# 3_3.net
KiCad netlist of a schematic drawn in EAGLE
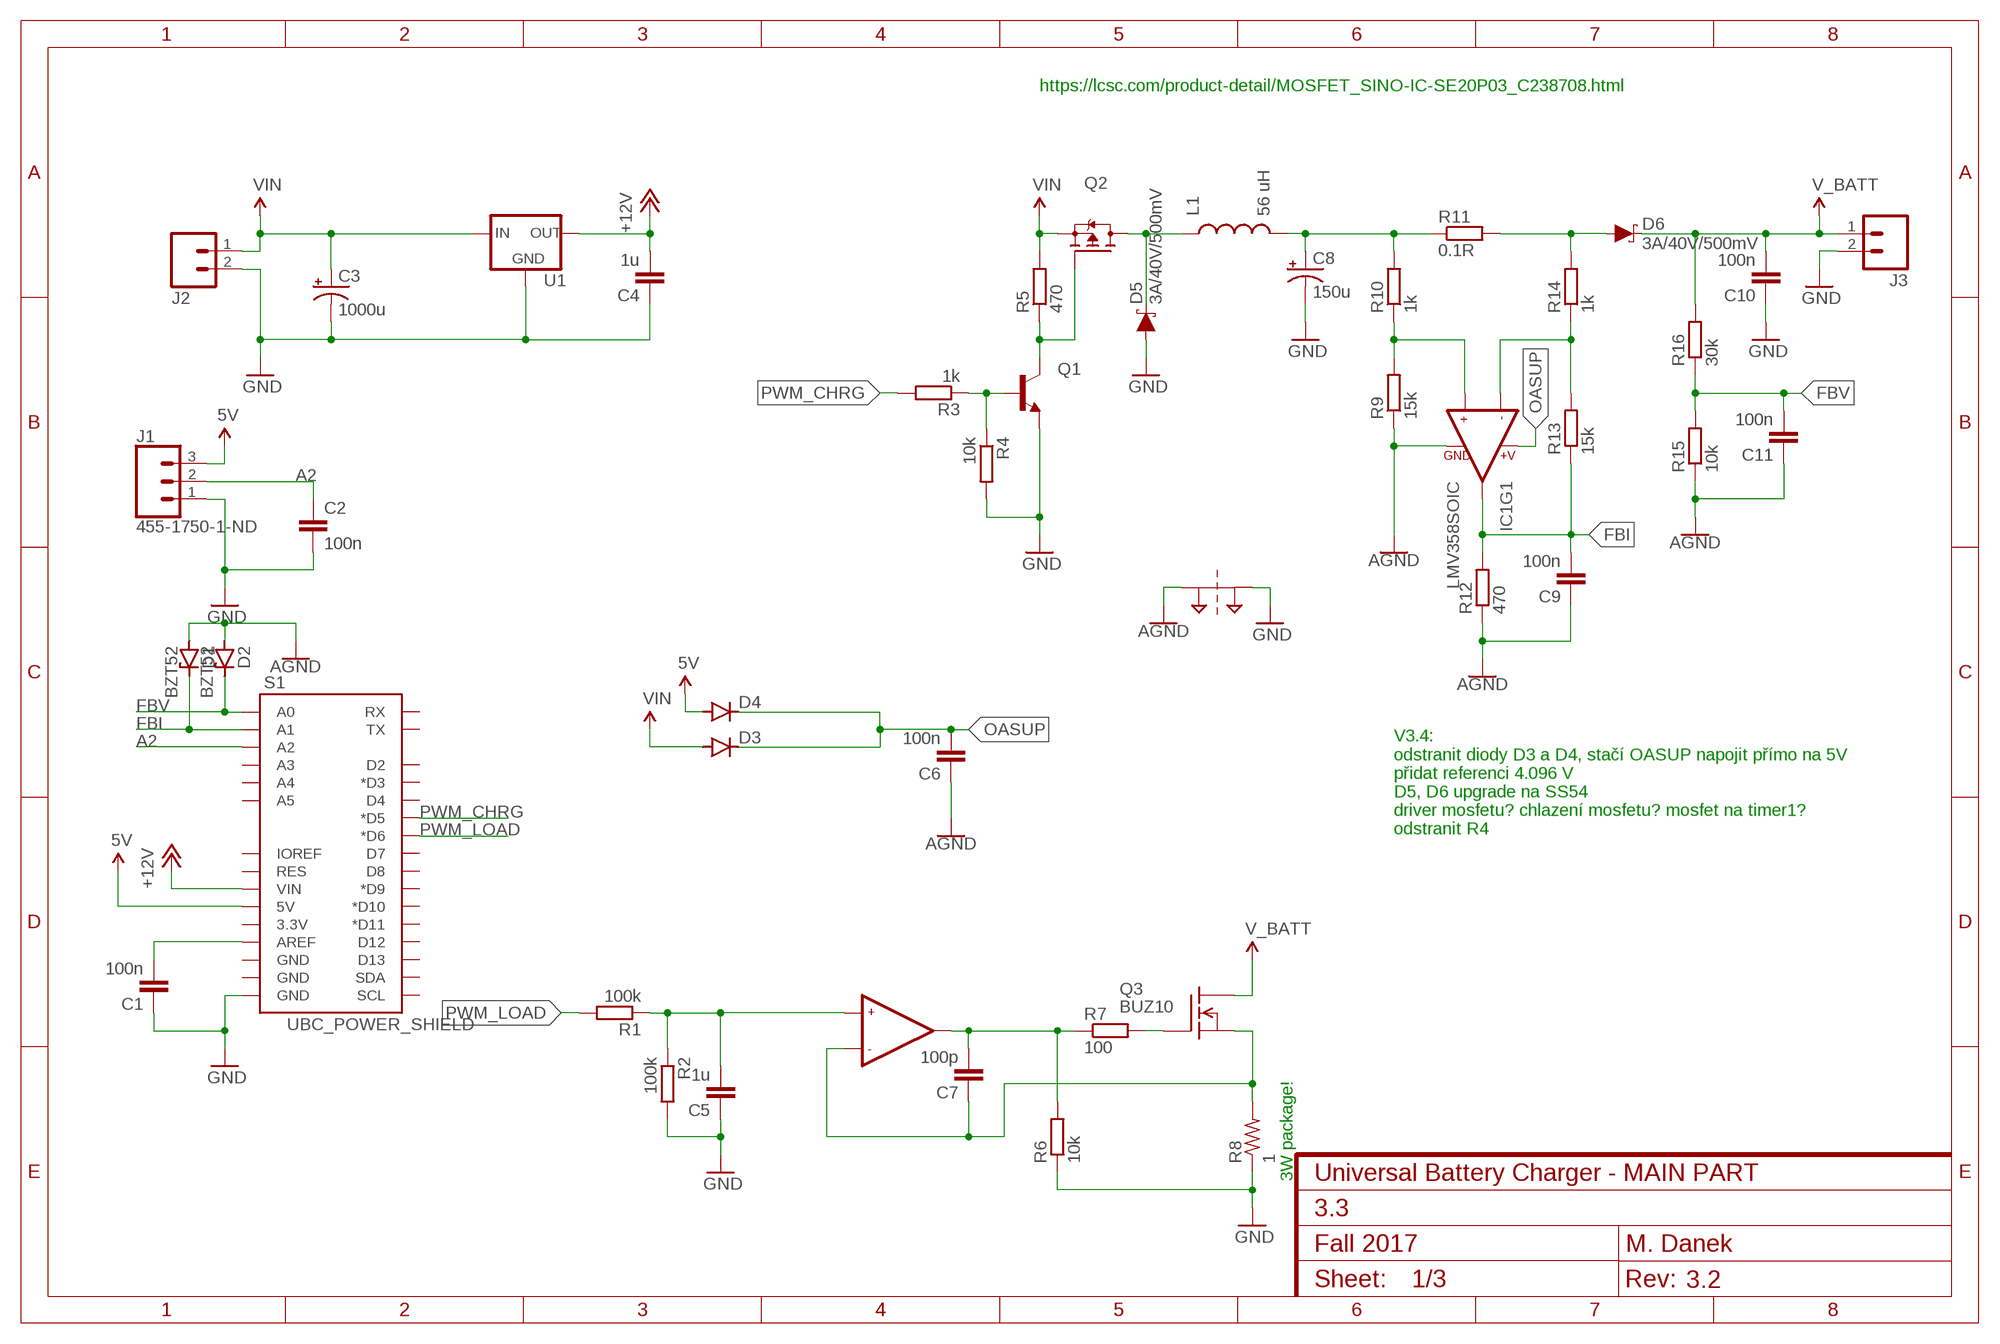
[diagram p0: schematic, sheet 1]
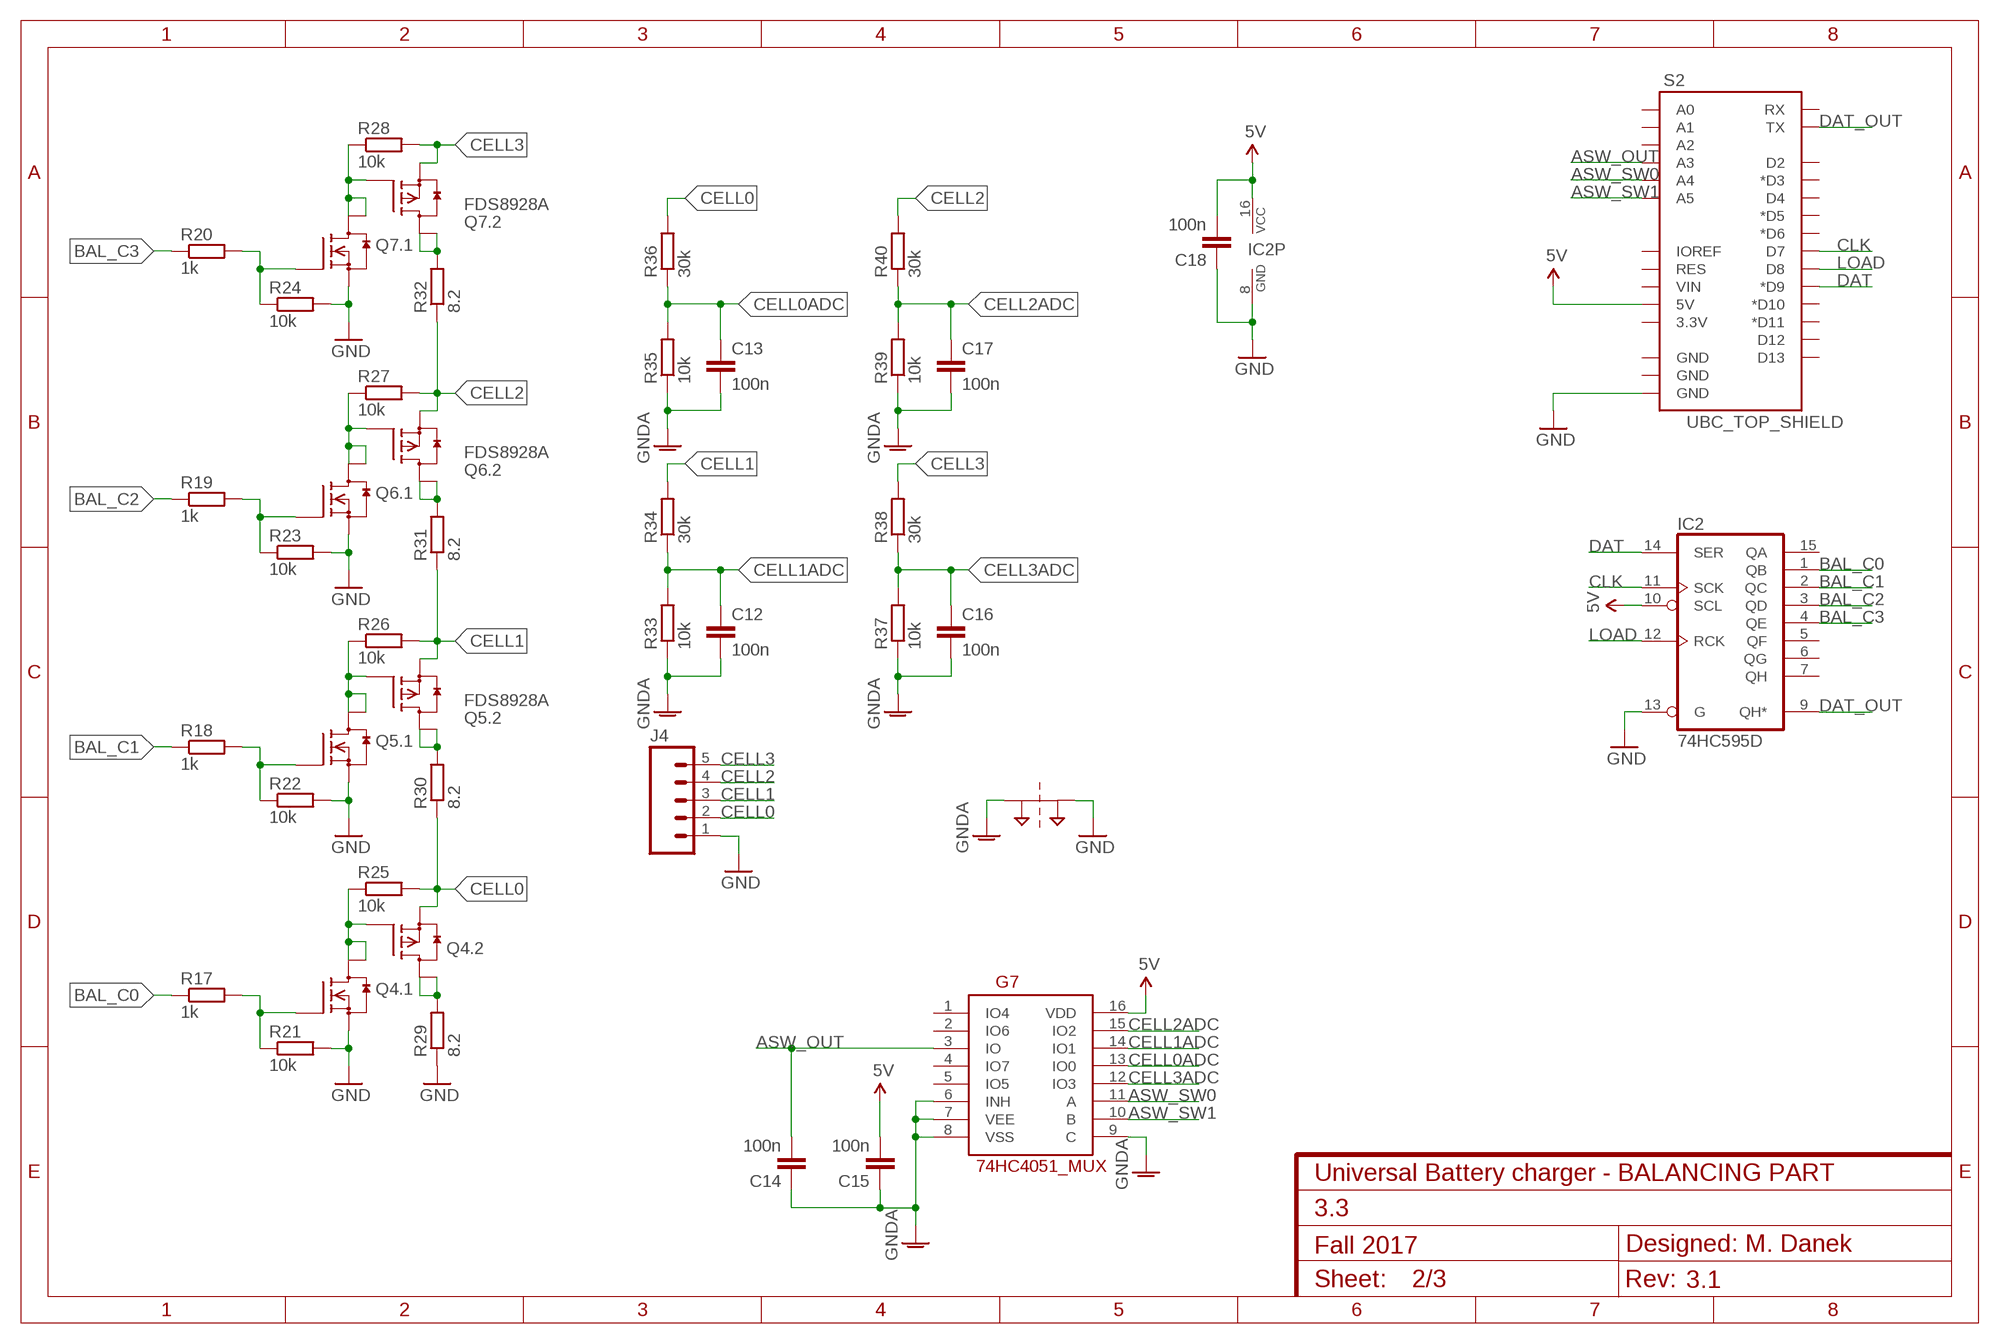
[diagram p1: schematic, sheet 2]
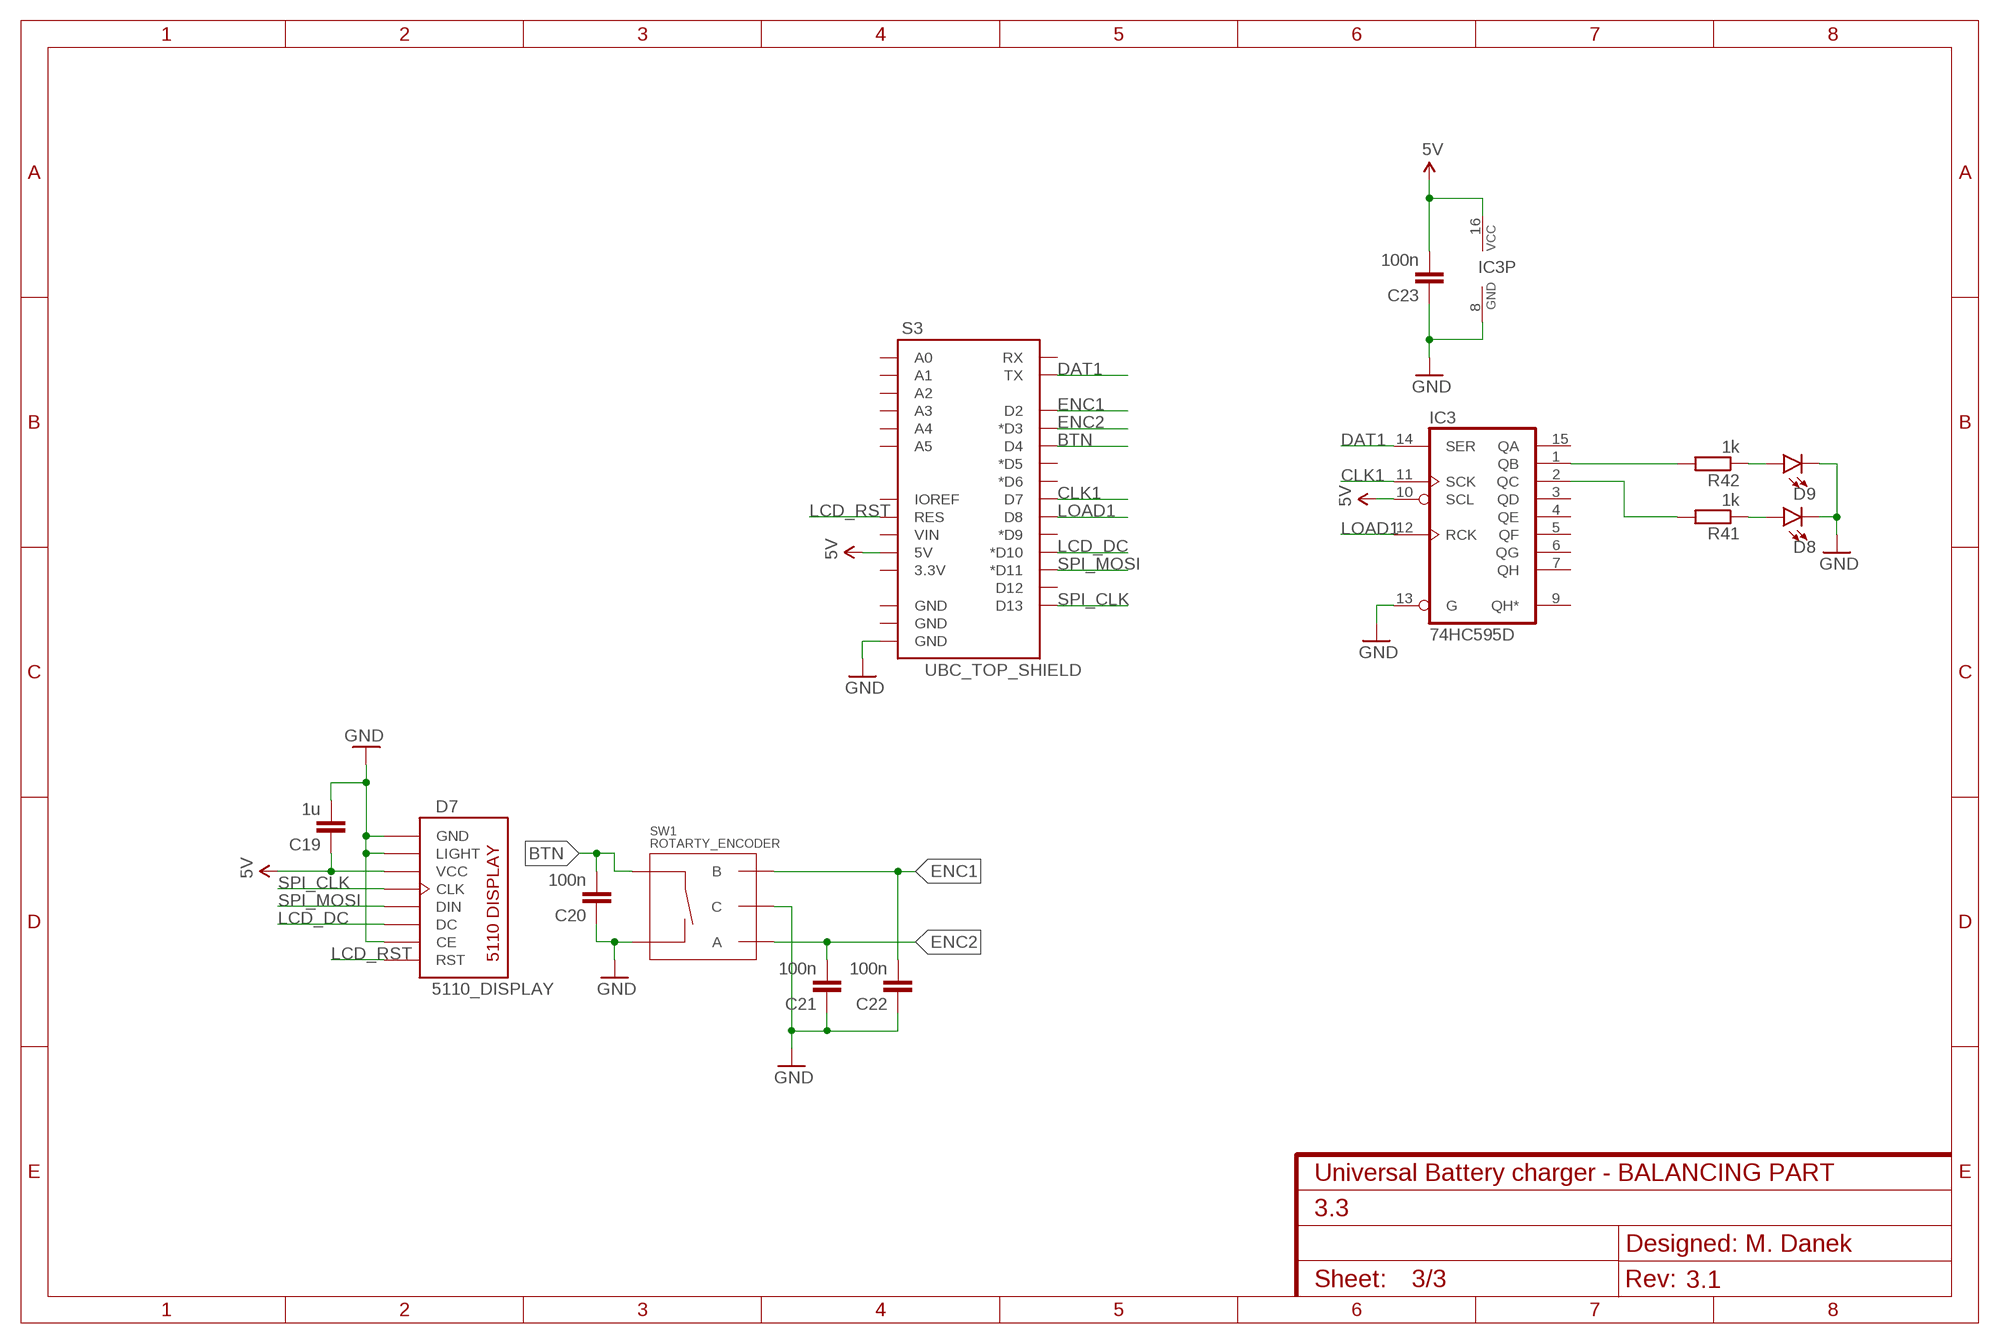
[diagram p2: schematic, sheet 3]

(export (version "E")
  (design (tool "Eeschema 10.0.6"))
  (components
    (comp (ref "C12")
      (value "100n")
      (footprint "eagle-import:C1206")
      (libsource (lib "eagle-import") (part "C-EUC1206"))
    )
    (comp (ref "C13")
      (value "100n")
      (footprint "eagle-import:C1206")
      (libsource (lib "eagle-import") (part "C-EUC1206"))
    )
    (comp (ref "C14")
      (value "100n")
      (footprint "eagle-import:C1206")
      (libsource (lib "eagle-import") (part "C-EUC1206"))
    )
    (comp (ref "C15")
      (value "100n")
      (footprint "eagle-import:C1206")
      (libsource (lib "eagle-import") (part "C-EUC1206"))
    )
    (comp (ref "C16")
      (value "100n")
      (footprint "eagle-import:C1206")
      (libsource (lib "eagle-import") (part "C-EUC1206"))
    )
    (comp (ref "C17")
      (value "100n")
      (footprint "eagle-import:C1206")
      (libsource (lib "eagle-import") (part "C-EUC1206"))
    )
    (comp (ref "C18")
      (value "100n")
      (footprint "eagle-import:1206")
      (libsource (lib "eagle-import") (part "CAP1206"))
    )
    (comp (ref "G7")
      (value "74HC4051_MUX")
      (footprint "eagle-import:SO16")
      (libsource (lib "eagle-import") (part "74HC4051_MUX"))
    )
    (comp (ref "IC2")
      (value "74HC595D")
      (footprint "eagle-import:SO16")
      (libsource (lib "eagle-import") (part "74595DHC"))
    )
    (comp (ref "J4")
      (value "M05PTH")
      (footprint "eagle-import:1X05")
      (libsource (lib "eagle-import") (part "M05PTH"))
    )
    (comp (ref "PT2")
      (value "2PT_GND_TIE")
      (footprint "eagle-import:2PT_GND_TIE")
      (libsource (lib "eagle-import") (part "2PT_GND_TIE"))
    )
    (comp (ref "Q4")
      (value "FDS8928A")
      (footprint "eagle-import:SO-8")
      (libsource (lib "eagle-import") (part "FDS8928A"))
    )
    (comp (ref "Q5")
      (value "FDS8928A")
      (footprint "eagle-import:SO-8")
      (libsource (lib "eagle-import") (part "FDS8928A"))
    )
    (comp (ref "Q6")
      (value "FDS8928A")
      (footprint "eagle-import:SO-8")
      (libsource (lib "eagle-import") (part "FDS8928A"))
    )
    (comp (ref "Q7")
      (value "FDS8928A")
      (footprint "eagle-import:SO-8")
      (libsource (lib "eagle-import") (part "FDS8928A"))
    )
    (comp (ref "R17")
      (value "1k")
      (footprint "eagle-import:R1206")
      (libsource (lib "eagle-import") (part "R-EU_R1206"))
    )
    (comp (ref "R18")
      (value "1k")
      (footprint "eagle-import:R1206")
      (libsource (lib "eagle-import") (part "R-EU_R1206"))
    )
    (comp (ref "R19")
      (value "1k")
      (footprint "eagle-import:R1206")
      (libsource (lib "eagle-import") (part "R-EU_R1206"))
    )
    (comp (ref "R20")
      (value "1k")
      (footprint "eagle-import:R1206")
      (libsource (lib "eagle-import") (part "R-EU_R1206"))
    )
    (comp (ref "R21")
      (value "10k")
      (footprint "eagle-import:R1206")
      (libsource (lib "eagle-import") (part "R-EU_R1206"))
    )
    (comp (ref "R22")
      (value "10k")
      (footprint "eagle-import:R1206")
      (libsource (lib "eagle-import") (part "R-EU_R1206"))
    )
    (comp (ref "R23")
      (value "10k")
      (footprint "eagle-import:R1206")
      (libsource (lib "eagle-import") (part "R-EU_R1206"))
    )
    (comp (ref "R24")
      (value "10k")
      (footprint "eagle-import:R1206")
      (libsource (lib "eagle-import") (part "R-EU_R1206"))
    )
    (comp (ref "R25")
      (value "10k")
      (footprint "eagle-import:R1206")
      (libsource (lib "eagle-import") (part "R-EU_R1206"))
    )
    (comp (ref "R26")
      (value "10k")
      (footprint "eagle-import:R1206")
      (libsource (lib "eagle-import") (part "R-EU_R1206"))
    )
    (comp (ref "R27")
      (value "10k")
      (footprint "eagle-import:R1206")
      (libsource (lib "eagle-import") (part "R-EU_R1206"))
    )
    (comp (ref "R28")
      (value "10k")
      (footprint "eagle-import:R1206")
      (libsource (lib "eagle-import") (part "R-EU_R1206"))
    )
    (comp (ref "R29")
      (value "8.2")
      (footprint "eagle-import:R2512")
      (libsource (lib "eagle-import") (part "R-EU_R2512"))
    )
    (comp (ref "R30")
      (value "8.2")
      (footprint "eagle-import:R2512")
      (libsource (lib "eagle-import") (part "R-EU_R2512"))
    )
    (comp (ref "R31")
      (value "8.2")
      (footprint "eagle-import:R2512")
      (libsource (lib "eagle-import") (part "R-EU_R2512"))
    )
    (comp (ref "R32")
      (value "8.2")
      (footprint "eagle-import:R2512")
      (libsource (lib "eagle-import") (part "R-EU_R2512"))
    )
    (comp (ref "R33")
      (value "10k")
      (footprint "eagle-import:R1206")
      (libsource (lib "eagle-import") (part "R-EU_R1206"))
    )
    (comp (ref "R34")
      (value "30k")
      (footprint "eagle-import:R1206")
      (libsource (lib "eagle-import") (part "R-EU_R1206"))
    )
    (comp (ref "R35")
      (value "10k")
      (footprint "eagle-import:R1206")
      (libsource (lib "eagle-import") (part "R-EU_R1206"))
    )
    (comp (ref "R36")
      (value "30k")
      (footprint "eagle-import:R1206")
      (libsource (lib "eagle-import") (part "R-EU_R1206"))
    )
    (comp (ref "R37")
      (value "10k")
      (footprint "eagle-import:R1206")
      (libsource (lib "eagle-import") (part "R-EU_R1206"))
    )
    (comp (ref "R38")
      (value "30k")
      (footprint "eagle-import:R1206")
      (libsource (lib "eagle-import") (part "R-EU_R1206"))
    )
    (comp (ref "R39")
      (value "10k")
      (footprint "eagle-import:R1206")
      (libsource (lib "eagle-import") (part "R-EU_R1206"))
    )
    (comp (ref "R40")
      (value "30k")
      (footprint "eagle-import:R1206")
      (libsource (lib "eagle-import") (part "R-EU_R1206"))
    )
    (comp (ref "S2")
      (value "UBC_TOP_SHIELD")
      (footprint "eagle-import:UBC_TOP")
      (libsource (lib "eagle-import") (part "UBC_TOP_SHIELD"))
    )
    (comp (ref "C1")
      (value "100n")
      (footprint "eagle-import:C1206")
      (libsource (lib "eagle-import") (part "C-EUC1206"))
    )
    (comp (ref "C2")
      (value "100n")
      (footprint "eagle-import:C1206")
      (libsource (lib "eagle-import") (part "C-EUC1206"))
    )
    (comp (ref "C3")
      (value "1000u")
      (footprint "eagle-import:CPOL-RADIAL-1000UF-25V")
      (libsource (lib "eagle-import") (part "SparkFun-Passives_CAP_POLPTH4"))
    )
    (comp (ref "C4")
      (value "1u")
      (footprint "eagle-import:C1206")
      (libsource (lib "eagle-import") (part "C-EUC1206"))
    )
    (comp (ref "C5")
      (value "1u")
      (footprint "eagle-import:C1206")
      (libsource (lib "eagle-import") (part "C-EUC1206"))
    )
    (comp (ref "C6")
      (value "100n")
      (footprint "eagle-import:C1206")
      (libsource (lib "eagle-import") (part "C-EUC1206"))
    )
    (comp (ref "C7")
      (value "100p")
      (footprint "eagle-import:C1206")
      (libsource (lib "eagle-import") (part "C-EUC1206"))
    )
    (comp (ref "C8")
      (value "150u")
      (footprint "eagle-import:CPOL-RADIAL-100UF-25V")
      (libsource (lib "eagle-import") (part "CAP_POLPTH1"))
    )
    (comp (ref "C9")
      (value "100n")
      (footprint "eagle-import:C1206")
      (libsource (lib "eagle-import") (part "C-EUC1206"))
    )
    (comp (ref "C10")
      (value "100n")
      (footprint "eagle-import:C1206")
      (libsource (lib "eagle-import") (part "C-EUC1206"))
    )
    (comp (ref "C11")
      (value "100n")
      (footprint "eagle-import:C1206")
      (libsource (lib "eagle-import") (part "C-EUC1206"))
    )
    (comp (ref "D1")
      (value "BZT52")
      (footprint "eagle-import:SOD80C")
      (libsource (lib "eagle-import") (part "ZENER-DIODESOD80C"))
    )
    (comp (ref "D2")
      (value "BZT52")
      (footprint "eagle-import:SOD80C")
      (libsource (lib "eagle-import") (part "ZENER-DIODESOD80C"))
    )
    (comp (ref "D3")
      (value "DIODE-MINIMELF")
      (footprint "eagle-import:MINIMELF")
      (libsource (lib "eagle-import") (part "DIODE-MINIMELF"))
    )
    (comp (ref "D4")
      (value "DIODE-MINIMELF")
      (footprint "eagle-import:MINIMELF")
      (libsource (lib "eagle-import") (part "DIODE-MINIMELF"))
    )
    (comp (ref "D5")
      (value "3A/40V/500mV")
      (footprint "eagle-import:SMA-DIODE")
      (libsource (lib "eagle-import") (part "DIODE-SCHOTTKY-B340A"))
    )
    (comp (ref "D6")
      (value "3A/40V/500mV")
      (footprint "eagle-import:SMA-DIODE")
      (libsource (lib "eagle-import") (part "DIODE-SCHOTTKY-B340A"))
    )
    (comp (ref "IC1")
      (value "LMV358SOIC")
      (footprint "eagle-import:SO08")
      (libsource (lib "eagle-import") (part "LMV358SOIC"))
    )
    (comp (ref "J1")
      (value "455-1750-1-ND")
      (footprint "eagle-import:1X03")
      (libsource (lib "eagle-import") (part "CONN_03"))
    )
    (comp (ref "J2")
      (value "M025MM")
      (footprint "eagle-import:SCREWTERMINAL-5MM-2")
      (libsource (lib "eagle-import") (part "M025MM"))
    )
    (comp (ref "J3")
      (value "M025MM")
      (footprint "eagle-import:SCREWTERMINAL-5MM-2")
      (libsource (lib "eagle-import") (part "M025MM"))
    )
    (comp (ref "L1")
      (value "56 uH")
      (footprint "eagle-import:CDRH125")
      (libsource (lib "eagle-import") (part "INDUCTORPWR"))
    )
    (comp (ref "PT1")
      (value "2PT_GND_TIE")
      (footprint "eagle-import:2PT_GND_TIE")
      (libsource (lib "eagle-import") (part "2PT_GND_TIE"))
    )
    (comp (ref "Q1")
      (value "2N3904-MMBT")
      (footprint "eagle-import:SOT23")
      (libsource (lib "eagle-import") (part "2N3904-MMBT"))
    )
    (comp (ref "Q2")
      (value "FDD4141TO252")
      (footprint "eagle-import:TO252")
      (libsource (lib "eagle-import") (part "FDD4141TO252"))
    )
    (comp (ref "Q3")
      (value "BUZ10")
      (footprint "eagle-import:TO220")
      (libsource (lib "eagle-import") (part "BUZ10"))
    )
    (comp (ref "R1")
      (value "100k")
      (footprint "eagle-import:R1206")
      (libsource (lib "eagle-import") (part "R-EU_R1206"))
    )
    (comp (ref "R2")
      (value "100k")
      (footprint "eagle-import:R1206")
      (libsource (lib "eagle-import") (part "R-EU_R1206"))
    )
    (comp (ref "R3")
      (value "1k")
      (footprint "eagle-import:R1206")
      (libsource (lib "eagle-import") (part "R-EU_R1206"))
    )
    (comp (ref "R4")
      (value "10k")
      (footprint "eagle-import:R1206")
      (libsource (lib "eagle-import") (part "R-EU_R1206"))
    )
    (comp (ref "R5")
      (value "470")
      (footprint "eagle-import:R1206")
      (libsource (lib "eagle-import") (part "R-EU_R1206"))
    )
    (comp (ref "R6")
      (value "10k")
      (footprint "eagle-import:R1206")
      (libsource (lib "eagle-import") (part "R-EU_R1206"))
    )
    (comp (ref "R7")
      (value "100")
      (footprint "eagle-import:R1206")
      (libsource (lib "eagle-import") (part "R-EU_R1206"))
    )
    (comp (ref "R8")
      (value "1")
      (footprint "eagle-import:0617_22")
      (libsource (lib "eagle-import") (part "R-US_0617/22"))
    )
    (comp (ref "R9")
      (value "15k")
      (footprint "eagle-import:R1206")
      (libsource (lib "eagle-import") (part "R-EU_R1206"))
    )
    (comp (ref "R10")
      (value "1k")
      (footprint "eagle-import:R1206")
      (libsource (lib "eagle-import") (part "R-EU_R1206"))
    )
    (comp (ref "R11")
      (value "0.1R")
      (footprint "eagle-import:0414_15")
      (libsource (lib "eagle-import") (part "R-EU_0414/15"))
    )
    (comp (ref "R12")
      (value "470")
      (footprint "eagle-import:R1206")
      (libsource (lib "eagle-import") (part "R-EU_R1206"))
    )
    (comp (ref "R13")
      (value "15k")
      (footprint "eagle-import:R1206")
      (libsource (lib "eagle-import") (part "R-EU_R1206"))
    )
    (comp (ref "R14")
      (value "1k")
      (footprint "eagle-import:R1206")
      (libsource (lib "eagle-import") (part "R-EU_R1206"))
    )
    (comp (ref "R15")
      (value "10k")
      (footprint "eagle-import:R1206")
      (libsource (lib "eagle-import") (part "R-EU_R1206"))
    )
    (comp (ref "R16")
      (value "30k")
      (footprint "eagle-import:R1206")
      (libsource (lib "eagle-import") (part "R-EU_R1206"))
    )
    (comp (ref "S1")
      (value "UBC_POWER_SHIELD")
      (footprint "eagle-import:UBC_POWER")
      (libsource (lib "eagle-import") (part "UBC_POWER_SHIELD"))
    )
    (comp (ref "U1")
      (value "V_REG_78XXSIDE")
      (footprint "eagle-import:78XXL")
      (libsource (lib "eagle-import") (part "V_REG_78XXSIDE"))
    )
    (comp (ref "C19")
      (value "1u")
      (footprint "eagle-import:1206")
      (libsource (lib "eagle-import") (part "CAP1206"))
    )
    (comp (ref "C20")
      (value "100n")
      (footprint "eagle-import:1206")
      (libsource (lib "eagle-import") (part "CAP1206"))
    )
    (comp (ref "C21")
      (value "100n")
      (footprint "eagle-import:1206")
      (libsource (lib "eagle-import") (part "CAP1206"))
    )
    (comp (ref "C22")
      (value "100n")
      (footprint "eagle-import:1206")
      (libsource (lib "eagle-import") (part "CAP1206"))
    )
    (comp (ref "C23")
      (value "100n")
      (footprint "eagle-import:1206")
      (libsource (lib "eagle-import") (part "CAP1206"))
    )
    (comp (ref "D7")
      (value "5110_DISPLAY")
      (footprint "eagle-import:5110_LAYOUT")
      (libsource (lib "eagle-import") (part "5110_DISPLAY"))
    )
    (comp (ref "D8")
      (value "LED5MM")
      (footprint "eagle-import:LED_5MM")
      (libsource (lib "eagle-import") (part "LED5MM"))
    )
    (comp (ref "D9")
      (value "LED5MM")
      (footprint "eagle-import:LED_5MM")
      (libsource (lib "eagle-import") (part "LED5MM"))
    )
    (comp (ref "IC3")
      (value "74HC595D")
      (footprint "eagle-import:SO16")
      (libsource (lib "eagle-import") (part "74595DHC"))
    )
    (comp (ref "R41")
      (value "1k")
      (footprint "eagle-import:R1206")
      (libsource (lib "eagle-import") (part "R-EU_R1206"))
    )
    (comp (ref "R42")
      (value "1k")
      (footprint "eagle-import:R1206")
      (libsource (lib "eagle-import") (part "R-EU_R1206"))
    )
    (comp (ref "S3")
      (value "UBC_TOP_SHIELD")
      (footprint "eagle-import:UBC_TOP")
      (libsource (lib "eagle-import") (part "UBC_TOP_SHIELD"))
    )
    (comp (ref "SW1")
      (value "ROTARTY_ENCODER")
      (footprint "eagle-import:ROTARY_ENC_PLAIN")
      (libsource (lib "eagle-import") (part "ROTARTY_ENCODER"))
    )
  )
  (nets
    (net (code "1") (name "+12V") (class "Default")
      (node (ref "C4") (pin "2") (pinfunction "2_2") (pintype "passive"))
      (node (ref "S1") (pin "VIN") (pinfunction "VIN_VIN") (pintype "bidirectional"))
      (node (ref "U1") (pin "OUT") (pinfunction "OUT_OUT") (pintype "passive"))
    )
    (net (code "2") (name "5V") (class "Default")
      (node (ref "C15") (pin "2") (pinfunction "2_2") (pintype "passive"))
      (node (ref "C18") (pin "2") (pinfunction "2_2") (pintype "passive"))
      (node (ref "C19") (pin "1") (pinfunction "1_1") (pintype "passive"))
      (node (ref "C23") (pin "2") (pinfunction "2_2") (pintype "passive"))
      (node (ref "D4") (pin "A") (pinfunction "A_A") (pintype "passive"))
      (node (ref "D7") (pin "VCC") (pinfunction "VCC_VCC") (pintype "bidirectional"))
      (node (ref "G7") (pin "16") (pinfunction "VDD_16") (pintype "bidirectional"))
      (node (ref "IC2") (pin "10") (pinfunction "SCL_10") (pintype "input"))
      (node (ref "IC2") (pin "16") (pinfunction "VCC_16") (pintype "power_in"))
      (node (ref "IC3") (pin "10") (pinfunction "SCL_10") (pintype "input"))
      (node (ref "IC3") (pin "16") (pinfunction "VCC_16") (pintype "power_in"))
      (node (ref "J1") (pin "3") (pinfunction "3_3") (pintype "passive"))
      (node (ref "S1") (pin "5V") (pinfunction "5V_5V") (pintype "bidirectional"))
      (node (ref "S2") (pin "5V") (pinfunction "5V_5V") (pintype "bidirectional"))
      (node (ref "S3") (pin "5V") (pinfunction "5V_5V") (pintype "bidirectional"))
    )
    (net (code "3") (name "A2") (class "Default")
      (node (ref "C2") (pin "1") (pinfunction "1_1") (pintype "passive"))
      (node (ref "J1") (pin "2") (pinfunction "2_2") (pintype "passive"))
      (node (ref "S1") (pin "A2") (pinfunction "A2_A2") (pintype "bidirectional"))
    )
    (net (code "4") (name "AGND") (class "Default")
      (node (ref "C11") (pin "1") (pinfunction "1_1") (pintype "passive"))
      (node (ref "C6") (pin "1") (pinfunction "1_1") (pintype "passive"))
      (node (ref "C9") (pin "1") (pinfunction "1_1") (pintype "passive"))
      (node (ref "D1") (pin "A") (pinfunction "A_A") (pintype "passive"))
      (node (ref "D2") (pin "A") (pinfunction "A_A") (pintype "passive"))
      (node (ref "IC1") (pin "4") (pinfunction "GND_4") (pintype "power_in"))
      (node (ref "PT1") (pin "P$1") (pinfunction "P$1_P$1") (pintype "bidirectional"))
      (node (ref "R12") (pin "1") (pinfunction "1_1") (pintype "passive"))
      (node (ref "R15") (pin "1") (pinfunction "1_1") (pintype "passive"))
      (node (ref "R9") (pin "1") (pinfunction "1_1") (pintype "passive"))
    )
    (net (code "5") (name "ASW_OUT") (class "Default")
      (node (ref "C14") (pin "2") (pinfunction "2_2") (pintype "passive"))
      (node (ref "G7") (pin "3") (pinfunction "IO_3") (pintype "bidirectional"))
      (node (ref "S2") (pin "A3") (pinfunction "A3_A3") (pintype "bidirectional"))
    )
    (net (code "6") (name "ASW_SW0") (class "Default")
      (node (ref "G7") (pin "11") (pinfunction "A_11") (pintype "bidirectional"))
      (node (ref "S2") (pin "A4") (pinfunction "A4_A4") (pintype "bidirectional"))
    )
    (net (code "7") (name "ASW_SW1") (class "Default")
      (node (ref "G7") (pin "10") (pinfunction "B_10") (pintype "bidirectional"))
      (node (ref "S2") (pin "A5") (pinfunction "A5_A5") (pintype "bidirectional"))
    )
    (net (code "8") (name "BAL_C0") (class "Default")
      (node (ref "IC2") (pin "1") (pinfunction "QB_1") (pintype "tri_state"))
      (node (ref "R17") (pin "1") (pinfunction "1_1") (pintype "passive"))
    )
    (net (code "9") (name "BAL_C1") (class "Default")
      (node (ref "IC2") (pin "2") (pinfunction "QC_2") (pintype "tri_state"))
      (node (ref "R18") (pin "1") (pinfunction "1_1") (pintype "passive"))
    )
    (net (code "10") (name "BAL_C2") (class "Default")
      (node (ref "IC2") (pin "3") (pinfunction "QD_3") (pintype "tri_state"))
      (node (ref "R19") (pin "1") (pinfunction "1_1") (pintype "passive"))
    )
    (net (code "11") (name "BAL_C3") (class "Default")
      (node (ref "IC2") (pin "4") (pinfunction "QE_4") (pintype "tri_state"))
      (node (ref "R20") (pin "1") (pinfunction "1_1") (pintype "passive"))
    )
    (net (code "12") (name "BTN") (class "Default")
      (node (ref "C20") (pin "2") (pinfunction "2_2") (pintype "passive"))
      (node (ref "S3") (pin "D4") (pinfunction "D4_D4") (pintype "bidirectional"))
      (node (ref "SW1") (pin "SW+") (pinfunction "SW+_SW+") (pintype "bidirectional"))
    )
    (net (code "13") (name "CELL0") (class "Default")
      (node (ref "J4") (pin "2") (pinfunction "2_2") (pintype "passive"))
      (node (ref "Q4") (pin "3") (pinfunction "S_3") (pintype "passive"))
      (node (ref "R25") (pin "2") (pinfunction "2_2") (pintype "passive"))
      (node (ref "R30") (pin "1") (pinfunction "1_1") (pintype "passive"))
      (node (ref "R36") (pin "2") (pinfunction "2_2") (pintype "passive"))
    )
    (net (code "14") (name "CELL0ADC") (class "Default")
      (node (ref "C13") (pin "1") (pinfunction "1_1") (pintype "passive"))
      (node (ref "G7") (pin "13") (pinfunction "IO0_13") (pintype "bidirectional"))
      (node (ref "R35") (pin "2") (pinfunction "2_2") (pintype "passive"))
      (node (ref "R36") (pin "1") (pinfunction "1_1") (pintype "passive"))
    )
    (net (code "15") (name "CELL1") (class "Default")
      (node (ref "J4") (pin "3") (pinfunction "3_3") (pintype "passive"))
      (node (ref "Q5") (pin "3") (pinfunction "S_3") (pintype "passive"))
      (node (ref "R26") (pin "2") (pinfunction "2_2") (pintype "passive"))
      (node (ref "R31") (pin "1") (pinfunction "1_1") (pintype "passive"))
      (node (ref "R34") (pin "2") (pinfunction "2_2") (pintype "passive"))
    )
    (net (code "16") (name "CELL1ADC") (class "Default")
      (node (ref "C12") (pin "1") (pinfunction "1_1") (pintype "passive"))
      (node (ref "G7") (pin "14") (pinfunction "IO1_14") (pintype "bidirectional"))
      (node (ref "R33") (pin "2") (pinfunction "2_2") (pintype "passive"))
      (node (ref "R34") (pin "1") (pinfunction "1_1") (pintype "passive"))
    )
    (net (code "17") (name "CELL2") (class "Default")
      (node (ref "J4") (pin "4") (pinfunction "4_4") (pintype "passive"))
      (node (ref "Q6") (pin "3") (pinfunction "S_3") (pintype "passive"))
      (node (ref "R27") (pin "2") (pinfunction "2_2") (pintype "passive"))
      (node (ref "R32") (pin "1") (pinfunction "1_1") (pintype "passive"))
      (node (ref "R40") (pin "2") (pinfunction "2_2") (pintype "passive"))
    )
    (net (code "18") (name "CELL2ADC") (class "Default")
      (node (ref "C17") (pin "1") (pinfunction "1_1") (pintype "passive"))
      (node (ref "G7") (pin "15") (pinfunction "IO2_15") (pintype "bidirectional"))
      (node (ref "R39") (pin "2") (pinfunction "2_2") (pintype "passive"))
      (node (ref "R40") (pin "1") (pinfunction "1_1") (pintype "passive"))
    )
    (net (code "19") (name "CELL3") (class "Default")
      (node (ref "J4") (pin "5") (pinfunction "5_5") (pintype "passive"))
      (node (ref "Q7") (pin "3") (pinfunction "S_3") (pintype "passive"))
      (node (ref "R28") (pin "2") (pinfunction "2_2") (pintype "passive"))
      (node (ref "R38") (pin "2") (pinfunction "2_2") (pintype "passive"))
    )
    (net (code "20") (name "CELL3ADC") (class "Default")
      (node (ref "C16") (pin "1") (pinfunction "1_1") (pintype "passive"))
      (node (ref "G7") (pin "12") (pinfunction "IO3_12") (pintype "bidirectional"))
      (node (ref "R37") (pin "2") (pinfunction "2_2") (pintype "passive"))
      (node (ref "R38") (pin "1") (pinfunction "1_1") (pintype "passive"))
    )
    (net (code "21") (name "CLK") (class "Default")
      (node (ref "IC2") (pin "11") (pinfunction "SCK_11") (pintype "input"))
      (node (ref "S2") (pin "D7") (pinfunction "D7_D7") (pintype "bidirectional"))
    )
    (net (code "22") (name "CLK1") (class "Default")
      (node (ref "IC3") (pin "11") (pinfunction "SCK_11") (pintype "input"))
      (node (ref "S3") (pin "D7") (pinfunction "D7_D7") (pintype "bidirectional"))
    )
    (net (code "23") (name "DAT") (class "Default")
      (node (ref "IC2") (pin "14") (pinfunction "SER_14") (pintype "input"))
      (node (ref "S2") (pin "D9") (pinfunction "*D9_D9") (pintype "bidirectional"))
    )
    (net (code "24") (name "DAT1") (class "Default")
      (node (ref "IC3") (pin "14") (pinfunction "SER_14") (pintype "input"))
      (node (ref "S3") (pin "TX") (pinfunction "TX_TX") (pintype "bidirectional"))
    )
    (net (code "25") (name "DAT_OUT") (class "Default")
      (node (ref "IC2") (pin "9") (pinfunction "QH*_9") (pintype "tri_state"))
      (node (ref "S2") (pin "TX") (pinfunction "TX_TX") (pintype "bidirectional"))
    )
    (net (code "26") (name "ENC1") (class "Default")
      (node (ref "C22") (pin "2") (pinfunction "2_2") (pintype "passive"))
      (node (ref "S3") (pin "D2") (pinfunction "D2_D2") (pintype "bidirectional"))
      (node (ref "SW1") (pin "B") (pinfunction "B_B") (pintype "bidirectional"))
    )
    (net (code "27") (name "ENC2") (class "Default")
      (node (ref "C21") (pin "2") (pinfunction "2_2") (pintype "passive"))
      (node (ref "S3") (pin "D3") (pinfunction "*D3_D3") (pintype "bidirectional"))
      (node (ref "SW1") (pin "A") (pinfunction "A_A") (pintype "bidirectional"))
    )
    (net (code "28") (name "FBI") (class "Default")
      (node (ref "C9") (pin "2") (pinfunction "2_2") (pintype "passive"))
      (node (ref "D1") (pin "C") (pinfunction "C_C") (pintype "passive"))
      (node (ref "IC1") (pin "1") (pinfunction "OUT1_1") (pintype "output"))
      (node (ref "R12") (pin "2") (pinfunction "2_2") (pintype "passive"))
      (node (ref "R13") (pin "1") (pinfunction "1_1") (pintype "passive"))
      (node (ref "S1") (pin "A1") (pinfunction "A1_A1") (pintype "bidirectional"))
    )
    (net (code "29") (name "FBV") (class "Default")
      (node (ref "C11") (pin "2") (pinfunction "2_2") (pintype "passive"))
      (node (ref "D2") (pin "C") (pinfunction "C_C") (pintype "passive"))
      (node (ref "R15") (pin "2") (pinfunction "2_2") (pintype "passive"))
      (node (ref "R16") (pin "1") (pinfunction "1_1") (pintype "passive"))
      (node (ref "S1") (pin "A0") (pinfunction "A0_A0") (pintype "bidirectional"))
    )
    (net (code "30") (name "GND") (class "Default")
      (node (ref "C1") (pin "1") (pinfunction "1_1") (pintype "passive"))
      (node (ref "C10") (pin "1") (pinfunction "1_1") (pintype "passive"))
      (node (ref "C18") (pin "1") (pinfunction "1_1") (pintype "passive"))
      (node (ref "C19") (pin "2") (pinfunction "2_2") (pintype "passive"))
      (node (ref "C2") (pin "2") (pinfunction "2_2") (pintype "passive"))
      (node (ref "C20") (pin "1") (pinfunction "1_1") (pintype "passive"))
      (node (ref "C21") (pin "1") (pinfunction "1_1") (pintype "passive"))
      (node (ref "C22") (pin "1") (pinfunction "1_1") (pintype "passive"))
      (node (ref "C23") (pin "1") (pinfunction "1_1") (pintype "passive"))
      (node (ref "C3") (pin "2") (pinfunction "-_2") (pintype "passive"))
      (node (ref "C4") (pin "1") (pinfunction "1_1") (pintype "passive"))
      (node (ref "C5") (pin "1") (pinfunction "1_1") (pintype "passive"))
      (node (ref "C8") (pin "2") (pinfunction "-_2") (pintype "passive"))
      (node (ref "D5") (pin "A") (pinfunction "A_A") (pintype "passive"))
      (node (ref "D7") (pin "CE") (pinfunction "CE_CE") (pintype "bidirectional"))
      (node (ref "D7") (pin "GND") (pinfunction "GND_GND") (pintype "bidirectional"))
      (node (ref "D7") (pin "LIGHT") (pinfunction "LIGHT_LIGHT") (pintype "bidirectional"))
      (node (ref "D8") (pin "K") (pinfunction "C_K") (pintype "passive"))
      (node (ref "D9") (pin "K") (pinfunction "C_K") (pintype "passive"))
      (node (ref "IC2") (pin "13") (pinfunction "G_13") (pintype "input"))
      (node (ref "IC2") (pin "8") (pinfunction "GND_8") (pintype "power_in"))
      (node (ref "IC3") (pin "13") (pinfunction "G_13") (pintype "input"))
      (node (ref "IC3") (pin "8") (pinfunction "GND_8") (pintype "power_in"))
      (node (ref "J1") (pin "1") (pinfunction "1_1") (pintype "passive"))
      (node (ref "J2") (pin "2") (pinfunction "2_2") (pintype "passive"))
      (node (ref "J3") (pin "2") (pinfunction "2_2") (pintype "passive"))
      (node (ref "J4") (pin "1") (pinfunction "1_1") (pintype "passive"))
      (node (ref "PT1") (pin "P$2") (pinfunction "P$2_P$2") (pintype "bidirectional"))
      (node (ref "PT2") (pin "P$2") (pinfunction "P$2_P$2") (pintype "bidirectional"))
      (node (ref "Q1") (pin "2") (pinfunction "E_2") (pintype "passive"))
      (node (ref "Q4") (pin "1") (pinfunction "S_1") (pintype "passive"))
      (node (ref "Q5") (pin "1") (pinfunction "S_1") (pintype "passive"))
      (node (ref "Q6") (pin "1") (pinfunction "S_1") (pintype "passive"))
      (node (ref "Q7") (pin "1") (pinfunction "S_1") (pintype "passive"))
      (node (ref "R2") (pin "2") (pinfunction "2_2") (pintype "passive"))
      (node (ref "R21") (pin "2") (pinfunction "2_2") (pintype "passive"))
      (node (ref "R22") (pin "2") (pinfunction "2_2") (pintype "passive"))
      (node (ref "R23") (pin "2") (pinfunction "2_2") (pintype "passive"))
      (node (ref "R24") (pin "2") (pinfunction "2_2") (pintype "passive"))
      (node (ref "R29") (pin "1") (pinfunction "1_1") (pintype "passive"))
      (node (ref "R4") (pin "2") (pinfunction "2_2") (pintype "passive"))
      (node (ref "R6") (pin "1") (pinfunction "1_1") (pintype "passive"))
      (node (ref "R8") (pin "1") (pinfunction "1_1") (pintype "passive"))
      (node (ref "S1") (pin "GND@0") (pinfunction "GND_GND@0") (pintype "bidirectional"))
      (node (ref "S2") (pin "GND@0") (pinfunction "GND_GND@0") (pintype "bidirectional"))
      (node (ref "S3") (pin "GND@0") (pinfunction "GND_GND@0") (pintype "bidirectional"))
      (node (ref "SW1") (pin "C") (pinfunction "C_C") (pintype "bidirectional"))
      (node (ref "SW1") (pin "SW-") (pinfunction "SW-_SW-") (pintype "bidirectional"))
      (node (ref "U1") (pin "GND") (pinfunction "GND_GND") (pintype "input"))
    )
    (net (code "31") (name "GNDA") (class "Default")
      (node (ref "C12") (pin "2") (pinfunction "2_2") (pintype "passive"))
      (node (ref "C13") (pin "2") (pinfunction "2_2") (pintype "passive"))
      (node (ref "C14") (pin "1") (pinfunction "1_1") (pintype "passive"))
      (node (ref "C15") (pin "1") (pinfunction "1_1") (pintype "passive"))
      (node (ref "C16") (pin "2") (pinfunction "2_2") (pintype "passive"))
      (node (ref "C17") (pin "2") (pinfunction "2_2") (pintype "passive"))
      (node (ref "G7") (pin "6") (pinfunction "INH_6") (pintype "bidirectional"))
      (node (ref "G7") (pin "7") (pinfunction "VEE_7") (pintype "bidirectional"))
      (node (ref "G7") (pin "8") (pinfunction "VSS_8") (pintype "bidirectional"))
      (node (ref "G7") (pin "9") (pinfunction "C_9") (pintype "bidirectional"))
      (node (ref "PT2") (pin "P$1") (pinfunction "P$1_P$1") (pintype "bidirectional"))
      (node (ref "R33") (pin "1") (pinfunction "1_1") (pintype "passive"))
      (node (ref "R35") (pin "1") (pinfunction "1_1") (pintype "passive"))
      (node (ref "R37") (pin "1") (pinfunction "1_1") (pintype "passive"))
      (node (ref "R39") (pin "1") (pinfunction "1_1") (pintype "passive"))
    )
    (net (code "32") (name "LCD_DC") (class "Default")
      (node (ref "D7") (pin "DC") (pinfunction "DC_DC") (pintype "bidirectional"))
      (node (ref "S3") (pin "D10") (pinfunction "*D10_D10") (pintype "bidirectional"))
    )
    (net (code "33") (name "LCD_RST") (class "Default")
      (node (ref "D7") (pin "RST") (pinfunction "RST_RST") (pintype "bidirectional"))
      (node (ref "S3") (pin "RES") (pinfunction "RES_RES") (pintype "bidirectional"))
    )
    (net (code "34") (name "LOAD") (class "Default")
      (node (ref "IC2") (pin "12") (pinfunction "RCK_12") (pintype "input"))
      (node (ref "S2") (pin "D8") (pinfunction "D8_D8") (pintype "bidirectional"))
    )
    (net (code "35") (name "LOAD1") (class "Default")
      (node (ref "IC3") (pin "12") (pinfunction "RCK_12") (pintype "input"))
      (node (ref "S3") (pin "D8") (pinfunction "D8_D8") (pintype "bidirectional"))
    )
    (net (code "36") (name "Net-(C1-Pad2)") (class "Default")
      (node (ref "C1") (pin "2") (pinfunction "2_2") (pintype "passive"))
      (node (ref "S1") (pin "AREF") (pinfunction "AREF_AREF") (pintype "bidirectional"))
    )
    (net (code "37") (name "Net-(C8-+)") (class "Default")
      (node (ref "C8") (pin "1") (pinfunction "+_1") (pintype "passive"))
      (node (ref "L1") (pin "2") (pinfunction "2_2") (pintype "passive"))
      (node (ref "R10") (pin "2") (pinfunction "2_2") (pintype "passive"))
      (node (ref "R11") (pin "1") (pinfunction "1_1") (pintype "passive"))
    )
    (net (code "38") (name "Net-(D6-PadA)") (class "Default")
      (node (ref "D6") (pin "A") (pinfunction "A_A") (pintype "passive"))
      (node (ref "R11") (pin "2") (pinfunction "2_2") (pintype "passive"))
      (node (ref "R14") (pin "2") (pinfunction "2_2") (pintype "passive"))
    )
    (net (code "39") (name "Net-(D8-PadA)") (class "Default")
      (node (ref "D8") (pin "A") (pinfunction "A_A") (pintype "passive"))
      (node (ref "R41") (pin "1") (pinfunction "1_1") (pintype "passive"))
    )
    (net (code "40") (name "Net-(D9-PadA)") (class "Default")
      (node (ref "D9") (pin "A") (pinfunction "A_A") (pintype "passive"))
      (node (ref "R42") (pin "1") (pinfunction "1_1") (pintype "passive"))
    )
    (net (code "41") (name "Net-(IC1A-+IN1)") (class "Default")
      (node (ref "IC1") (pin "3") (pinfunction "+IN1_3") (pintype "input"))
      (node (ref "R10") (pin "1") (pinfunction "1_1") (pintype "passive"))
      (node (ref "R9") (pin "2") (pinfunction "2_2") (pintype "passive"))
    )
    (net (code "42") (name "Net-(IC1A--IN1)") (class "Default")
      (node (ref "IC1") (pin "2") (pinfunction "-IN1_2") (pintype "input"))
      (node (ref "R13") (pin "2") (pinfunction "2_2") (pintype "passive"))
      (node (ref "R14") (pin "1") (pinfunction "1_1") (pintype "passive"))
    )
    (net (code "43") (name "Net-(IC1B-+IN2)") (class "Default")
      (node (ref "C5") (pin "2") (pinfunction "2_2") (pintype "passive"))
      (node (ref "IC1") (pin "5") (pinfunction "+IN2_5") (pintype "input"))
      (node (ref "R1") (pin "1") (pinfunction "1_1") (pintype "passive"))
      (node (ref "R2") (pin "1") (pinfunction "1_1") (pintype "passive"))
    )
    (net (code "44") (name "Net-(IC1B--IN2)") (class "Default")
      (node (ref "C7") (pin "1") (pinfunction "1_1") (pintype "passive"))
      (node (ref "IC1") (pin "6") (pinfunction "-IN2_6") (pintype "input"))
      (node (ref "Q3") (pin "3") (pinfunction "S_3") (pintype "passive"))
      (node (ref "R8") (pin "2") (pinfunction "2_2") (pintype "passive"))
    )
    (net (code "45") (name "Net-(IC1B-OUT2)") (class "Default")
      (node (ref "C7") (pin "2") (pinfunction "2_2") (pintype "passive"))
      (node (ref "IC1") (pin "7") (pinfunction "OUT2_7") (pintype "output"))
      (node (ref "R6") (pin "2") (pinfunction "2_2") (pintype "passive"))
      (node (ref "R7") (pin "1") (pinfunction "1_1") (pintype "passive"))
    )
    (net (code "46") (name "Net-(IC3A-QB)") (class "Default")
      (node (ref "IC3") (pin "1") (pinfunction "QB_1") (pintype "tri_state"))
      (node (ref "R42") (pin "2") (pinfunction "2_2") (pintype "passive"))
    )
    (net (code "47") (name "Net-(IC3A-QC)") (class "Default")
      (node (ref "IC3") (pin "2") (pinfunction "QC_2") (pintype "tri_state"))
      (node (ref "R41") (pin "2") (pinfunction "2_2") (pintype "passive"))
    )
    (net (code "48") (name "Net-(Q1-B)") (class "Default")
      (node (ref "Q1") (pin "1") (pinfunction "B_1") (pintype "passive"))
      (node (ref "R3") (pin "1") (pinfunction "1_1") (pintype "passive"))
      (node (ref "R4") (pin "1") (pinfunction "1_1") (pintype "passive"))
    )
    (net (code "49") (name "Net-(Q1-C)") (class "Default")
      (node (ref "Q1") (pin "3") (pinfunction "C_3") (pintype "passive"))
      (node (ref "Q2") (pin "1") (pinfunction "G_1") (pintype "passive"))
      (node (ref "R5") (pin "1") (pinfunction "1_1") (pintype "passive"))
    )
    (net (code "50") (name "Net-(Q2-D)") (class "Default")
      (node (ref "D5") (pin "C") (pinfunction "C_C") (pintype "passive"))
      (node (ref "L1") (pin "1") (pinfunction "1_1") (pintype "passive"))
      (node (ref "Q2") (pin "3") (pinfunction "D_3") (pintype "passive"))
    )
    (net (code "51") (name "Net-(Q3-G)") (class "Default")
      (node (ref "Q3") (pin "1") (pinfunction "G_1") (pintype "passive"))
      (node (ref "R7") (pin "2") (pinfunction "2_2") (pintype "passive"))
    )
    (net (code "52") (name "Net-(Q4A-G)") (class "Default")
      (node (ref "Q4") (pin "2") (pinfunction "G_2") (pintype "passive"))
      (node (ref "R17") (pin "2") (pinfunction "2_2") (pintype "passive"))
      (node (ref "R21") (pin "1") (pinfunction "1_1") (pintype "passive"))
    )
    (net (code "53") (name "Net-(Q4B-D-Pad5)") (class "Default")
      (node (ref "Q4") (pin "5") (pinfunction "D_5") (pintype "passive"))
      (node (ref "Q4") (pin "6") (pinfunction "D_6") (pintype "passive"))
      (node (ref "R29") (pin "2") (pinfunction "2_2") (pintype "passive"))
    )
    (net (code "54") (name "Net-(Q4B-G)") (class "Default")
      (node (ref "Q4") (pin "4") (pinfunction "G_4") (pintype "passive"))
      (node (ref "Q4") (pin "7") (pinfunction "D_7") (pintype "passive"))
      (node (ref "Q4") (pin "8") (pinfunction "D_8") (pintype "passive"))
      (node (ref "R25") (pin "1") (pinfunction "1_1") (pintype "passive"))
    )
    (net (code "55") (name "Net-(Q5A-G)") (class "Default")
      (node (ref "Q5") (pin "2") (pinfunction "G_2") (pintype "passive"))
      (node (ref "R18") (pin "2") (pinfunction "2_2") (pintype "passive"))
      (node (ref "R22") (pin "1") (pinfunction "1_1") (pintype "passive"))
    )
    (net (code "56") (name "Net-(Q5B-D-Pad5)") (class "Default")
      (node (ref "Q5") (pin "5") (pinfunction "D_5") (pintype "passive"))
      (node (ref "Q5") (pin "6") (pinfunction "D_6") (pintype "passive"))
      (node (ref "R30") (pin "2") (pinfunction "2_2") (pintype "passive"))
    )
    (net (code "57") (name "Net-(Q5B-G)") (class "Default")
      (node (ref "Q5") (pin "4") (pinfunction "G_4") (pintype "passive"))
      (node (ref "Q5") (pin "7") (pinfunction "D_7") (pintype "passive"))
      (node (ref "Q5") (pin "8") (pinfunction "D_8") (pintype "passive"))
      (node (ref "R26") (pin "1") (pinfunction "1_1") (pintype "passive"))
    )
    (net (code "58") (name "Net-(Q6A-G)") (class "Default")
      (node (ref "Q6") (pin "2") (pinfunction "G_2") (pintype "passive"))
      (node (ref "R19") (pin "2") (pinfunction "2_2") (pintype "passive"))
      (node (ref "R23") (pin "1") (pinfunction "1_1") (pintype "passive"))
    )
    (net (code "59") (name "Net-(Q6B-D-Pad5)") (class "Default")
      (node (ref "Q6") (pin "5") (pinfunction "D_5") (pintype "passive"))
      (node (ref "Q6") (pin "6") (pinfunction "D_6") (pintype "passive"))
      (node (ref "R31") (pin "2") (pinfunction "2_2") (pintype "passive"))
    )
    (net (code "60") (name "Net-(Q6B-G)") (class "Default")
      (node (ref "Q6") (pin "4") (pinfunction "G_4") (pintype "passive"))
      (node (ref "Q6") (pin "7") (pinfunction "D_7") (pintype "passive"))
      (node (ref "Q6") (pin "8") (pinfunction "D_8") (pintype "passive"))
      (node (ref "R27") (pin "1") (pinfunction "1_1") (pintype "passive"))
    )
    (net (code "61") (name "Net-(Q7A-G)") (class "Default")
      (node (ref "Q7") (pin "2") (pinfunction "G_2") (pintype "passive"))
      (node (ref "R20") (pin "2") (pinfunction "2_2") (pintype "passive"))
      (node (ref "R24") (pin "1") (pinfunction "1_1") (pintype "passive"))
    )
    (net (code "62") (name "Net-(Q7B-D-Pad5)") (class "Default")
      (node (ref "Q7") (pin "5") (pinfunction "D_5") (pintype "passive"))
      (node (ref "Q7") (pin "6") (pinfunction "D_6") (pintype "passive"))
      (node (ref "R32") (pin "2") (pinfunction "2_2") (pintype "passive"))
    )
    (net (code "63") (name "Net-(Q7B-G)") (class "Default")
      (node (ref "Q7") (pin "4") (pinfunction "G_4") (pintype "passive"))
      (node (ref "Q7") (pin "7") (pinfunction "D_7") (pintype "passive"))
      (node (ref "Q7") (pin "8") (pinfunction "D_8") (pintype "passive"))
      (node (ref "R28") (pin "1") (pinfunction "1_1") (pintype "passive"))
    )
    (net (code "64") (name "OASUP") (class "Default")
      (node (ref "C6") (pin "2") (pinfunction "2_2") (pintype "passive"))
      (node (ref "D3") (pin "C") (pinfunction "C_C") (pintype "passive"))
      (node (ref "D4") (pin "C") (pinfunction "C_C") (pintype "passive"))
      (node (ref "IC1") (pin "8") (pinfunction "+V_8") (pintype "power_in"))
    )
    (net (code "65") (name "PWM_CHRG") (class "Default")
      (node (ref "R3") (pin "2") (pinfunction "2_2") (pintype "passive"))
      (node (ref "S1") (pin "D5") (pinfunction "*D5_D5") (pintype "bidirectional"))
    )
    (net (code "66") (name "PWM_LOAD") (class "Default")
      (node (ref "R1") (pin "2") (pinfunction "2_2") (pintype "passive"))
      (node (ref "S1") (pin "D6") (pinfunction "*D6_D6") (pintype "bidirectional"))
    )
    (net (code "67") (name "SPI_CLK") (class "Default")
      (node (ref "D7") (pin "CLK") (pinfunction "CLK_CLK") (pintype "bidirectional"))
      (node (ref "S3") (pin "D13") (pinfunction "D13_D13") (pintype "bidirectional"))
    )
    (net (code "68") (name "SPI_MOSI") (class "Default")
      (node (ref "D7") (pin "DIN") (pinfunction "DIN_DIN") (pintype "bidirectional"))
      (node (ref "S3") (pin "D11") (pinfunction "*D11_D11") (pintype "bidirectional"))
    )
    (net (code "69") (name "VIN") (class "Default")
      (node (ref "C3") (pin "1") (pinfunction "+_1") (pintype "passive"))
      (node (ref "D3") (pin "A") (pinfunction "A_A") (pintype "passive"))
      (node (ref "J2") (pin "1") (pinfunction "1_1") (pintype "passive"))
      (node (ref "Q2") (pin "2") (pinfunction "S_2") (pintype "passive"))
      (node (ref "R5") (pin "2") (pinfunction "2_2") (pintype "passive"))
      (node (ref "U1") (pin "IN") (pinfunction "IN_IN") (pintype "input"))
    )
    (net (code "70") (name "V_BATT") (class "Default")
      (node (ref "C10") (pin "2") (pinfunction "2_2") (pintype "passive"))
      (node (ref "D6") (pin "C") (pinfunction "C_C") (pintype "passive"))
      (node (ref "J3") (pin "1") (pinfunction "1_1") (pintype "passive"))
      (node (ref "Q3") (pin "2") (pinfunction "D_2") (pintype "passive"))
      (node (ref "R16") (pin "2") (pinfunction "2_2") (pintype "passive"))
    )
    (net (code "71") (name "unconnected-(G7-IO4-Pad1)") (class "Default")
      (node (ref "G7") (pin "1") (pinfunction "IO4_1") (pintype "bidirectional"))
    )
    (net (code "72") (name "unconnected-(G7-IO5-Pad5)") (class "Default")
      (node (ref "G7") (pin "5") (pinfunction "IO5_5") (pintype "bidirectional"))
    )
    (net (code "73") (name "unconnected-(G7-IO6-Pad2)") (class "Default")
      (node (ref "G7") (pin "2") (pinfunction "IO6_2") (pintype "bidirectional"))
    )
    (net (code "74") (name "unconnected-(G7-IO7-Pad4)") (class "Default")
      (node (ref "G7") (pin "4") (pinfunction "IO7_4") (pintype "bidirectional"))
    )
    (net (code "75") (name "unconnected-(IC2A-QA-Pad15)") (class "Default")
      (node (ref "IC2") (pin "15") (pinfunction "QA_15") (pintype "tri_state"))
    )
    (net (code "76") (name "unconnected-(IC2A-QF-Pad5)") (class "Default")
      (node (ref "IC2") (pin "5") (pinfunction "QF_5") (pintype "tri_state"))
    )
    (net (code "77") (name "unconnected-(IC2A-QG-Pad6)") (class "Default")
      (node (ref "IC2") (pin "6") (pinfunction "QG_6") (pintype "tri_state"))
    )
    (net (code "78") (name "unconnected-(IC2A-QH-Pad7)") (class "Default")
      (node (ref "IC2") (pin "7") (pinfunction "QH_7") (pintype "tri_state"))
    )
    (net (code "79") (name "unconnected-(IC3A-QA-Pad15)") (class "Default")
      (node (ref "IC3") (pin "15") (pinfunction "QA_15") (pintype "tri_state"))
    )
    (net (code "80") (name "unconnected-(IC3A-QD-Pad3)") (class "Default")
      (node (ref "IC3") (pin "3") (pinfunction "QD_3") (pintype "tri_state"))
    )
    (net (code "81") (name "unconnected-(IC3A-QE-Pad4)") (class "Default")
      (node (ref "IC3") (pin "4") (pinfunction "QE_4") (pintype "tri_state"))
    )
    (net (code "82") (name "unconnected-(IC3A-QF-Pad5)") (class "Default")
      (node (ref "IC3") (pin "5") (pinfunction "QF_5") (pintype "tri_state"))
    )
    (net (code "83") (name "unconnected-(IC3A-QG-Pad6)") (class "Default")
      (node (ref "IC3") (pin "6") (pinfunction "QG_6") (pintype "tri_state"))
    )
    (net (code "84") (name "unconnected-(IC3A-QH*-Pad9)") (class "Default")
      (node (ref "IC3") (pin "9") (pinfunction "QH*_9") (pintype "tri_state"))
    )
    (net (code "85") (name "unconnected-(IC3A-QH-Pad7)") (class "Default")
      (node (ref "IC3") (pin "7") (pinfunction "QH_7") (pintype "tri_state"))
    )
    (net (code "86") (name "unconnected-(S1-*D3-PadD3)") (class "Default")
      (node (ref "S1") (pin "D3") (pinfunction "*D3_D3") (pintype "bidirectional"))
    )
    (net (code "87") (name "unconnected-(S1-*D9-PadD9)") (class "Default")
      (node (ref "S1") (pin "D9") (pinfunction "*D9_D9") (pintype "bidirectional"))
    )
    (net (code "88") (name "unconnected-(S1-*D10-PadD10)") (class "Default")
      (node (ref "S1") (pin "D10") (pinfunction "*D10_D10") (pintype "bidirectional"))
    )
    (net (code "89") (name "unconnected-(S1-*D11-PadD11)") (class "Default")
      (node (ref "S1") (pin "D11") (pinfunction "*D11_D11") (pintype "bidirectional"))
    )
    (net (code "90") (name "unconnected-(S1-GND-PadGND@1)") (class "Default")
      (node (ref "S1") (pin "GND@1") (pinfunction "GND_GND@1") (pintype "bidirectional"))
    )
    (net (code "91") (name "unconnected-(S1-GND-PadGND@2)") (class "Default")
      (node (ref "S1") (pin "GND@2") (pinfunction "GND_GND@2") (pintype "bidirectional"))
    )
    (net (code "92") (name "unconnected-(S1-Pad3.3V)") (class "Default")
      (node (ref "S1") (pin "3.3V") (pinfunction "3.3V_3.3V") (pintype "bidirectional"))
    )
    (net (code "93") (name "unconnected-(S1-PadA3)") (class "Default")
      (node (ref "S1") (pin "A3") (pinfunction "A3_A3") (pintype "bidirectional"))
    )
    (net (code "94") (name "unconnected-(S1-PadA4)") (class "Default")
      (node (ref "S1") (pin "A4") (pinfunction "A4_A4") (pintype "bidirectional"))
    )
    (net (code "95") (name "unconnected-(S1-PadA5)") (class "Default")
      (node (ref "S1") (pin "A5") (pinfunction "A5_A5") (pintype "bidirectional"))
    )
    (net (code "96") (name "unconnected-(S1-PadD2)") (class "Default")
      (node (ref "S1") (pin "D2") (pinfunction "D2_D2") (pintype "bidirectional"))
    )
    (net (code "97") (name "unconnected-(S1-PadD4)") (class "Default")
      (node (ref "S1") (pin "D4") (pinfunction "D4_D4") (pintype "bidirectional"))
    )
    (net (code "98") (name "unconnected-(S1-PadD7)") (class "Default")
      (node (ref "S1") (pin "D7") (pinfunction "D7_D7") (pintype "bidirectional"))
    )
    (net (code "99") (name "unconnected-(S1-PadD8)") (class "Default")
      (node (ref "S1") (pin "D8") (pinfunction "D8_D8") (pintype "bidirectional"))
    )
    (net (code "100") (name "unconnected-(S1-PadD12)") (class "Default")
      (node (ref "S1") (pin "D12") (pinfunction "D12_D12") (pintype "bidirectional"))
    )
    (net (code "101") (name "unconnected-(S1-PadD13)") (class "Default")
      (node (ref "S1") (pin "D13") (pinfunction "D13_D13") (pintype "bidirectional"))
    )
    (net (code "102") (name "unconnected-(S1-PadIOREF)") (class "Default")
      (node (ref "S1") (pin "IOREF") (pinfunction "IOREF_IOREF") (pintype "bidirectional"))
    )
    (net (code "103") (name "unconnected-(S1-PadRES)") (class "Default")
      (node (ref "S1") (pin "RES") (pinfunction "RES_RES") (pintype "bidirectional"))
    )
    (net (code "104") (name "unconnected-(S1-PadRX)") (class "Default")
      (node (ref "S1") (pin "RX") (pinfunction "RX_RX") (pintype "bidirectional"))
    )
    (net (code "105") (name "unconnected-(S1-PadSCL)") (class "Default")
      (node (ref "S1") (pin "SCL") (pinfunction "SCL_SCL") (pintype "bidirectional"))
    )
    (net (code "106") (name "unconnected-(S1-PadSDA)") (class "Default")
      (node (ref "S1") (pin "SDA") (pinfunction "SDA_SDA") (pintype "bidirectional"))
    )
    (net (code "107") (name "unconnected-(S1-PadTX)") (class "Default")
      (node (ref "S1") (pin "TX") (pinfunction "TX_TX") (pintype "bidirectional"))
    )
    (net (code "108") (name "unconnected-(S2-*D3-PadD3)") (class "Default")
      (node (ref "S2") (pin "D3") (pinfunction "*D3_D3") (pintype "bidirectional"))
    )
    (net (code "109") (name "unconnected-(S2-*D5-PadD5)") (class "Default")
      (node (ref "S2") (pin "D5") (pinfunction "*D5_D5") (pintype "bidirectional"))
    )
    (net (code "110") (name "unconnected-(S2-*D6-PadD6)") (class "Default")
      (node (ref "S2") (pin "D6") (pinfunction "*D6_D6") (pintype "bidirectional"))
    )
    (net (code "111") (name "unconnected-(S2-*D10-PadD10)") (class "Default")
      (node (ref "S2") (pin "D10") (pinfunction "*D10_D10") (pintype "bidirectional"))
    )
    (net (code "112") (name "unconnected-(S2-*D11-PadD11)") (class "Default")
      (node (ref "S2") (pin "D11") (pinfunction "*D11_D11") (pintype "bidirectional"))
    )
    (net (code "113") (name "unconnected-(S2-GND-PadGND@1)") (class "Default")
      (node (ref "S2") (pin "GND@1") (pinfunction "GND_GND@1") (pintype "bidirectional"))
    )
    (net (code "114") (name "unconnected-(S2-GND-PadGND@2)") (class "Default")
      (node (ref "S2") (pin "GND@2") (pinfunction "GND_GND@2") (pintype "bidirectional"))
    )
    (net (code "115") (name "unconnected-(S2-Pad3.3V)") (class "Default")
      (node (ref "S2") (pin "3.3V") (pinfunction "3.3V_3.3V") (pintype "bidirectional"))
    )
    (net (code "116") (name "unconnected-(S2-PadA0)") (class "Default")
      (node (ref "S2") (pin "A0") (pinfunction "A0_A0") (pintype "bidirectional"))
    )
    (net (code "117") (name "unconnected-(S2-PadA1)") (class "Default")
      (node (ref "S2") (pin "A1") (pinfunction "A1_A1") (pintype "bidirectional"))
    )
    (net (code "118") (name "unconnected-(S2-PadA2)") (class "Default")
      (node (ref "S2") (pin "A2") (pinfunction "A2_A2") (pintype "bidirectional"))
    )
    (net (code "119") (name "unconnected-(S2-PadD2)") (class "Default")
      (node (ref "S2") (pin "D2") (pinfunction "D2_D2") (pintype "bidirectional"))
    )
    (net (code "120") (name "unconnected-(S2-PadD4)") (class "Default")
      (node (ref "S2") (pin "D4") (pinfunction "D4_D4") (pintype "bidirectional"))
    )
    (net (code "121") (name "unconnected-(S2-PadD12)") (class "Default")
      (node (ref "S2") (pin "D12") (pinfunction "D12_D12") (pintype "bidirectional"))
    )
    (net (code "122") (name "unconnected-(S2-PadD13)") (class "Default")
      (node (ref "S2") (pin "D13") (pinfunction "D13_D13") (pintype "bidirectional"))
    )
    (net (code "123") (name "unconnected-(S2-PadIOREF)") (class "Default")
      (node (ref "S2") (pin "IOREF") (pinfunction "IOREF_IOREF") (pintype "bidirectional"))
    )
    (net (code "124") (name "unconnected-(S2-PadRES)") (class "Default")
      (node (ref "S2") (pin "RES") (pinfunction "RES_RES") (pintype "bidirectional"))
    )
    (net (code "125") (name "unconnected-(S2-PadRX)") (class "Default")
      (node (ref "S2") (pin "RX") (pinfunction "RX_RX") (pintype "bidirectional"))
    )
    (net (code "126") (name "unconnected-(S2-PadVIN)") (class "Default")
      (node (ref "S2") (pin "VIN") (pinfunction "VIN_VIN") (pintype "bidirectional"))
    )
    (net (code "127") (name "unconnected-(S3-*D5-PadD5)") (class "Default")
      (node (ref "S3") (pin "D5") (pinfunction "*D5_D5") (pintype "bidirectional"))
    )
    (net (code "128") (name "unconnected-(S3-*D6-PadD6)") (class "Default")
      (node (ref "S3") (pin "D6") (pinfunction "*D6_D6") (pintype "bidirectional"))
    )
    (net (code "129") (name "unconnected-(S3-*D9-PadD9)") (class "Default")
      (node (ref "S3") (pin "D9") (pinfunction "*D9_D9") (pintype "bidirectional"))
    )
    (net (code "130") (name "unconnected-(S3-GND-PadGND@1)") (class "Default")
      (node (ref "S3") (pin "GND@1") (pinfunction "GND_GND@1") (pintype "bidirectional"))
    )
    (net (code "131") (name "unconnected-(S3-GND-PadGND@2)") (class "Default")
      (node (ref "S3") (pin "GND@2") (pinfunction "GND_GND@2") (pintype "bidirectional"))
    )
    (net (code "132") (name "unconnected-(S3-Pad3.3V)") (class "Default")
      (node (ref "S3") (pin "3.3V") (pinfunction "3.3V_3.3V") (pintype "bidirectional"))
    )
    (net (code "133") (name "unconnected-(S3-PadA0)") (class "Default")
      (node (ref "S3") (pin "A0") (pinfunction "A0_A0") (pintype "bidirectional"))
    )
    (net (code "134") (name "unconnected-(S3-PadA1)") (class "Default")
      (node (ref "S3") (pin "A1") (pinfunction "A1_A1") (pintype "bidirectional"))
    )
    (net (code "135") (name "unconnected-(S3-PadA2)") (class "Default")
      (node (ref "S3") (pin "A2") (pinfunction "A2_A2") (pintype "bidirectional"))
    )
    (net (code "136") (name "unconnected-(S3-PadA3)") (class "Default")
      (node (ref "S3") (pin "A3") (pinfunction "A3_A3") (pintype "bidirectional"))
    )
    (net (code "137") (name "unconnected-(S3-PadA4)") (class "Default")
      (node (ref "S3") (pin "A4") (pinfunction "A4_A4") (pintype "bidirectional"))
    )
    (net (code "138") (name "unconnected-(S3-PadA5)") (class "Default")
      (node (ref "S3") (pin "A5") (pinfunction "A5_A5") (pintype "bidirectional"))
    )
    (net (code "139") (name "unconnected-(S3-PadD12)") (class "Default")
      (node (ref "S3") (pin "D12") (pinfunction "D12_D12") (pintype "bidirectional"))
    )
    (net (code "140") (name "unconnected-(S3-PadIOREF)") (class "Default")
      (node (ref "S3") (pin "IOREF") (pinfunction "IOREF_IOREF") (pintype "bidirectional"))
    )
    (net (code "141") (name "unconnected-(S3-PadRX)") (class "Default")
      (node (ref "S3") (pin "RX") (pinfunction "RX_RX") (pintype "bidirectional"))
    )
    (net (code "142") (name "unconnected-(S3-PadVIN)") (class "Default")
      (node (ref "S3") (pin "VIN") (pinfunction "VIN_VIN") (pintype "bidirectional"))
    )
  )
)
